# macron.net
KiCad netlist of a schematic drawn in EAGLE
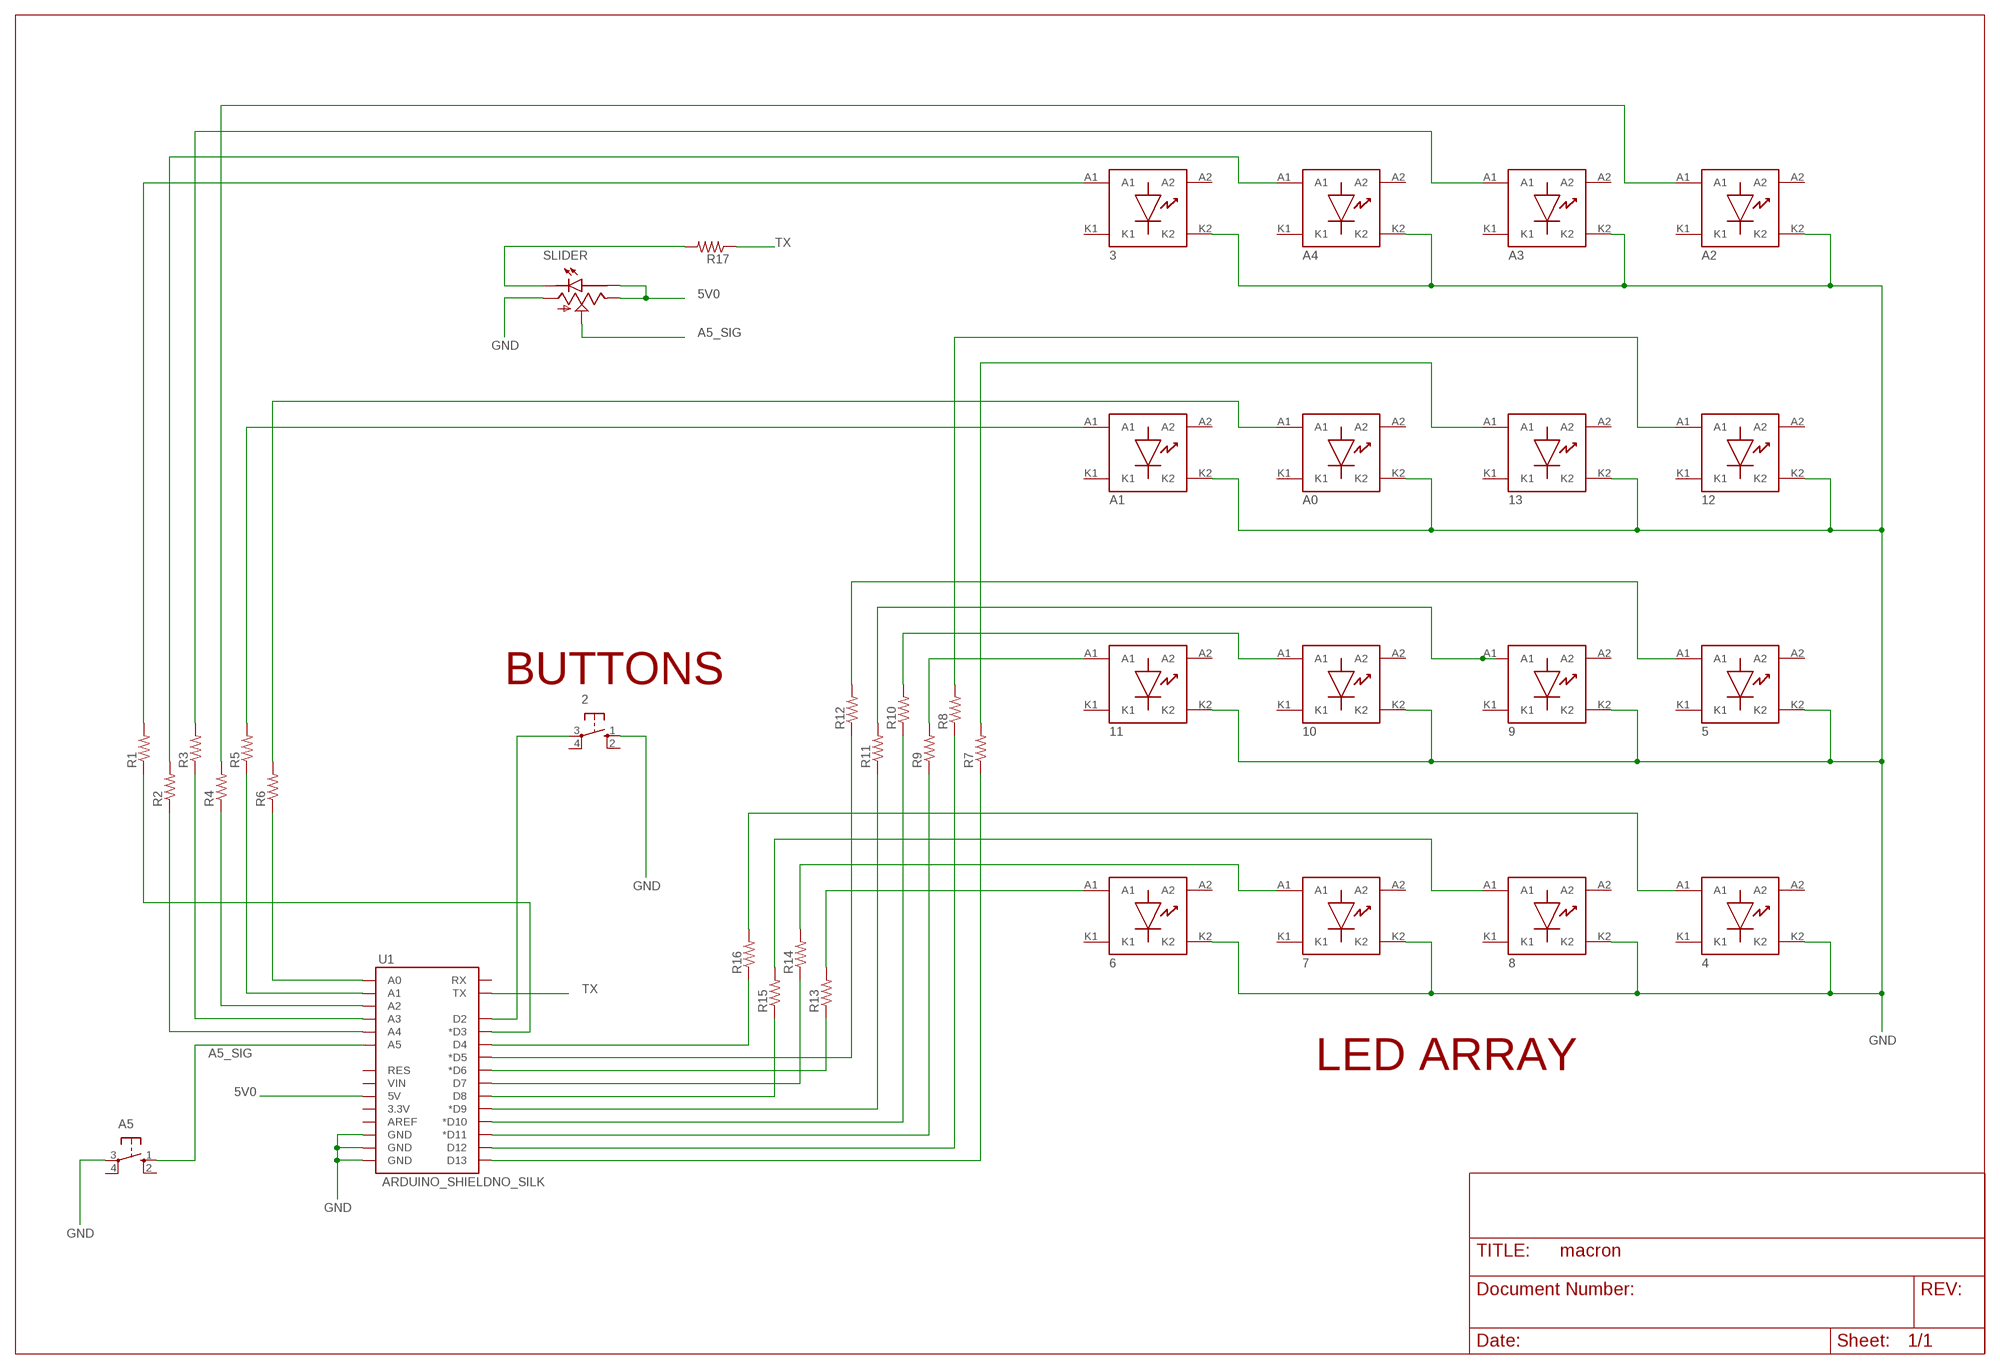
[diagram p0: schematic, sheet 1]

(export (version "E")
  (design (tool "Eeschema 10.0.6"))
  (components
    (comp (ref "2")
      (value "10-XX")
      (footprint "eagle-import:B3F-10XX")
      (fields (field (name "MPN") "B3F-1000"))
      (libsource (lib "eagle-import") (part "10-XX"))
    )
    (comp (ref "3")
      (value "LED_SMT")
      (footprint "eagle-import:AVAGO-SMT-LED")
      (libsource (lib "eagle-import") (part "LED_SMT"))
    )
    (comp (ref "4")
      (value "LED_SMT")
      (footprint "eagle-import:AVAGO-SMT-LED")
      (libsource (lib "eagle-import") (part "LED_SMT"))
    )
    (comp (ref "5")
      (value "LED_SMT")
      (footprint "eagle-import:AVAGO-SMT-LED")
      (libsource (lib "eagle-import") (part "LED_SMT"))
    )
    (comp (ref "6")
      (value "LED_SMT")
      (footprint "eagle-import:AVAGO-SMT-LED")
      (libsource (lib "eagle-import") (part "LED_SMT"))
    )
    (comp (ref "7")
      (value "LED_SMT")
      (footprint "eagle-import:AVAGO-SMT-LED")
      (libsource (lib "eagle-import") (part "LED_SMT"))
    )
    (comp (ref "8")
      (value "LED_SMT")
      (footprint "eagle-import:AVAGO-SMT-LED")
      (libsource (lib "eagle-import") (part "LED_SMT"))
    )
    (comp (ref "9")
      (value "LED_SMT")
      (footprint "eagle-import:AVAGO-SMT-LED")
      (libsource (lib "eagle-import") (part "LED_SMT"))
    )
    (comp (ref "10")
      (value "LED_SMT")
      (footprint "eagle-import:AVAGO-SMT-LED")
      (libsource (lib "eagle-import") (part "LED_SMT"))
    )
    (comp (ref "11")
      (value "LED_SMT")
      (footprint "eagle-import:AVAGO-SMT-LED")
      (libsource (lib "eagle-import") (part "LED_SMT"))
    )
    (comp (ref "12")
      (value "LED_SMT")
      (footprint "eagle-import:AVAGO-SMT-LED")
      (libsource (lib "eagle-import") (part "LED_SMT"))
    )
    (comp (ref "13")
      (value "LED_SMT")
      (footprint "eagle-import:AVAGO-SMT-LED")
      (libsource (lib "eagle-import") (part "LED_SMT"))
    )
    (comp (ref "A0")
      (value "LED_SMT")
      (footprint "eagle-import:AVAGO-SMT-LED")
      (libsource (lib "eagle-import") (part "LED_SMT"))
    )
    (comp (ref "A1")
      (value "LED_SMT")
      (footprint "eagle-import:AVAGO-SMT-LED")
      (libsource (lib "eagle-import") (part "LED_SMT"))
    )
    (comp (ref "A2")
      (value "LED_SMT")
      (footprint "eagle-import:AVAGO-SMT-LED")
      (libsource (lib "eagle-import") (part "LED_SMT"))
    )
    (comp (ref "A3")
      (value "LED_SMT")
      (footprint "eagle-import:AVAGO-SMT-LED")
      (libsource (lib "eagle-import") (part "LED_SMT"))
    )
    (comp (ref "A4")
      (value "LED_SMT")
      (footprint "eagle-import:AVAGO-SMT-LED")
      (libsource (lib "eagle-import") (part "LED_SMT"))
    )
    (comp (ref "A5")
      (value "10-XX")
      (footprint "eagle-import:B3F-10XX")
      (fields (field (name "MPN") "B3F-1000"))
      (libsource (lib "eagle-import") (part "10-XX"))
    )
    (comp (ref "R1")
      (value "R-US_0204/7")
      (footprint "eagle-import:0204_7")
      (libsource (lib "eagle-import") (part "R-US_0204/7"))
    )
    (comp (ref "R2")
      (value "R-US_0204/7")
      (footprint "eagle-import:0204_7")
      (libsource (lib "eagle-import") (part "R-US_0204/7"))
    )
    (comp (ref "R3")
      (value "R-US_0204/7")
      (footprint "eagle-import:0204_7")
      (libsource (lib "eagle-import") (part "R-US_0204/7"))
    )
    (comp (ref "R4")
      (value "R-US_0204/7")
      (footprint "eagle-import:0204_7")
      (libsource (lib "eagle-import") (part "R-US_0204/7"))
    )
    (comp (ref "R5")
      (value "R-US_0204/7")
      (footprint "eagle-import:0204_7")
      (libsource (lib "eagle-import") (part "R-US_0204/7"))
    )
    (comp (ref "R6")
      (value "R-US_0204/7")
      (footprint "eagle-import:0204_7")
      (libsource (lib "eagle-import") (part "R-US_0204/7"))
    )
    (comp (ref "R7")
      (value "R-US_0204/7")
      (footprint "eagle-import:0204_7")
      (libsource (lib "eagle-import") (part "R-US_0204/7"))
    )
    (comp (ref "R8")
      (value "R-US_0204/7")
      (footprint "eagle-import:0204_7")
      (libsource (lib "eagle-import") (part "R-US_0204/7"))
    )
    (comp (ref "R9")
      (value "R-US_0204/7")
      (footprint "eagle-import:0204_7")
      (libsource (lib "eagle-import") (part "R-US_0204/7"))
    )
    (comp (ref "R10")
      (value "R-US_0204/7")
      (footprint "eagle-import:0204_7")
      (libsource (lib "eagle-import") (part "R-US_0204/7"))
    )
    (comp (ref "R11")
      (value "R-US_0204/7")
      (footprint "eagle-import:0204_7")
      (libsource (lib "eagle-import") (part "R-US_0204/7"))
    )
    (comp (ref "R12")
      (value "R-US_0204/7")
      (footprint "eagle-import:0204_7")
      (libsource (lib "eagle-import") (part "R-US_0204/7"))
    )
    (comp (ref "R13")
      (value "R-US_0204/7")
      (footprint "eagle-import:0204_7")
      (libsource (lib "eagle-import") (part "R-US_0204/7"))
    )
    (comp (ref "R14")
      (value "R-US_0204/7")
      (footprint "eagle-import:0204_7")
      (libsource (lib "eagle-import") (part "R-US_0204/7"))
    )
    (comp (ref "R15")
      (value "R-US_0204/7")
      (footprint "eagle-import:0204_7")
      (libsource (lib "eagle-import") (part "R-US_0204/7"))
    )
    (comp (ref "R16")
      (value "R-US_0204/7")
      (footprint "eagle-import:0204_7")
      (libsource (lib "eagle-import") (part "R-US_0204/7"))
    )
    (comp (ref "R17")
      (value "R-US_0204/7")
      (footprint "eagle-import:0204_7")
      (libsource (lib "eagle-import") (part "R-US_0204/7"))
    )
    (comp (ref "SLIDER")
      (value "BOURNS_LED_SLIDER")
      (footprint "eagle-import:BOURNS_45MM_LED_SLIDE_POT")
      (libsource (lib "eagle-import") (part "BOURNS_LED_SLIDER"))
    )
    (comp (ref "U1")
      (value "ARDUINO_SHIELDNO_SILK")
      (footprint "eagle-import:DUEMILANOVE_VIAS")
      (libsource (lib "eagle-import") (part "ARDUINO_SHIELDNO_SILK"))
    )
  )
  (nets
    (net (code "1") (name "/5V0") (class "Default")
      (node (ref "SLIDER") (pin "HIGH_END") (pinfunction "HIGH_HIGH_END") (pintype "passive"))
      (node (ref "SLIDER") (pin "LED+") (pinfunction "A1_LED+") (pintype "passive"))
      (node (ref "U1") (pin "5V") (pinfunction "5V_5V") (pintype "bidirectional"))
    )
    (net (code "2") (name "/A5_SIG") (class "Default")
      (node (ref "A5") (pin "1") (pinfunction "S_1") (pintype "passive"))
      (node (ref "SLIDER") (pin "WIPER") (pinfunction "WIPER_WIPER") (pintype "passive"))
      (node (ref "U1") (pin "A5") (pinfunction "A5_A5") (pintype "bidirectional"))
    )
    (net (code "3") (name "/GND") (class "Default")
      (node (ref "10") (pin "K2") (pinfunction "K2_K2") (pintype "passive"))
      (node (ref "11") (pin "K2") (pinfunction "K2_K2") (pintype "passive"))
      (node (ref "12") (pin "K2") (pinfunction "K2_K2") (pintype "passive"))
      (node (ref "13") (pin "K2") (pinfunction "K2_K2") (pintype "passive"))
      (node (ref "2") (pin "1") (pinfunction "S_1") (pintype "passive"))
      (node (ref "3") (pin "K2") (pinfunction "K2_K2") (pintype "passive"))
      (node (ref "4") (pin "K2") (pinfunction "K2_K2") (pintype "passive"))
      (node (ref "5") (pin "K2") (pinfunction "K2_K2") (pintype "passive"))
      (node (ref "6") (pin "K2") (pinfunction "K2_K2") (pintype "passive"))
      (node (ref "7") (pin "K2") (pinfunction "K2_K2") (pintype "passive"))
      (node (ref "8") (pin "K2") (pinfunction "K2_K2") (pintype "passive"))
      (node (ref "9") (pin "K2") (pinfunction "K2_K2") (pintype "passive"))
      (node (ref "A0") (pin "K2") (pinfunction "K2_K2") (pintype "passive"))
      (node (ref "A1") (pin "K2") (pinfunction "K2_K2") (pintype "passive"))
      (node (ref "A2") (pin "K2") (pinfunction "K2_K2") (pintype "passive"))
      (node (ref "A3") (pin "K2") (pinfunction "K2_K2") (pintype "passive"))
      (node (ref "A4") (pin "K2") (pinfunction "K2_K2") (pintype "passive"))
      (node (ref "A5") (pin "3") (pinfunction "P_3") (pintype "passive"))
      (node (ref "SLIDER") (pin "LOW_END") (pinfunction "LOW_LOW_END") (pintype "passive"))
      (node (ref "U1") (pin "GND@0") (pinfunction "GND_GND@0") (pintype "bidirectional"))
      (node (ref "U1") (pin "GND@1") (pinfunction "GND_GND@1") (pintype "bidirectional"))
      (node (ref "U1") (pin "GND@2") (pinfunction "GND_GND@2") (pintype "bidirectional"))
    )
    (net (code "4") (name "/TX") (class "Default")
      (node (ref "R17") (pin "1") (pinfunction "1_1") (pintype "passive"))
      (node (ref "U1") (pin "TX") (pinfunction "TX_TX") (pintype "bidirectional"))
    )
    (net (code "5") (name "Net-(2-P)") (class "Default")
      (node (ref "2") (pin "3") (pinfunction "P_3") (pintype "passive"))
      (node (ref "U1") (pin "D2") (pinfunction "D2_D2") (pintype "bidirectional"))
    )
    (net (code "6") (name "Net-(3-PadA1)") (class "Default")
      (node (ref "3") (pin "A1") (pinfunction "A1_A1") (pintype "passive"))
      (node (ref "R1") (pin "2") (pinfunction "2_2") (pintype "passive"))
    )
    (net (code "7") (name "Net-(4-PadA1)") (class "Default")
      (node (ref "4") (pin "A1") (pinfunction "A1_A1") (pintype "passive"))
      (node (ref "R16") (pin "2") (pinfunction "2_2") (pintype "passive"))
    )
    (net (code "8") (name "Net-(5-PadA1)") (class "Default")
      (node (ref "5") (pin "A1") (pinfunction "A1_A1") (pintype "passive"))
      (node (ref "R12") (pin "2") (pinfunction "2_2") (pintype "passive"))
    )
    (net (code "9") (name "Net-(6-PadA1)") (class "Default")
      (node (ref "6") (pin "A1") (pinfunction "A1_A1") (pintype "passive"))
      (node (ref "R13") (pin "2") (pinfunction "2_2") (pintype "passive"))
    )
    (net (code "10") (name "Net-(7-PadA1)") (class "Default")
      (node (ref "7") (pin "A1") (pinfunction "A1_A1") (pintype "passive"))
      (node (ref "R14") (pin "2") (pinfunction "2_2") (pintype "passive"))
    )
    (net (code "11") (name "Net-(8-PadA1)") (class "Default")
      (node (ref "8") (pin "A1") (pinfunction "A1_A1") (pintype "passive"))
      (node (ref "R15") (pin "2") (pinfunction "2_2") (pintype "passive"))
    )
    (net (code "12") (name "Net-(9-PadA1)") (class "Default")
      (node (ref "9") (pin "A1") (pinfunction "A1_A1") (pintype "passive"))
      (node (ref "R11") (pin "2") (pinfunction "2_2") (pintype "passive"))
    )
    (net (code "13") (name "Net-(10-PadA1)") (class "Default")
      (node (ref "10") (pin "A1") (pinfunction "A1_A1") (pintype "passive"))
      (node (ref "R10") (pin "2") (pinfunction "2_2") (pintype "passive"))
    )
    (net (code "14") (name "Net-(11-PadA1)") (class "Default")
      (node (ref "11") (pin "A1") (pinfunction "A1_A1") (pintype "passive"))
      (node (ref "R9") (pin "2") (pinfunction "2_2") (pintype "passive"))
    )
    (net (code "15") (name "Net-(12-PadA1)") (class "Default")
      (node (ref "12") (pin "A1") (pinfunction "A1_A1") (pintype "passive"))
      (node (ref "R8") (pin "2") (pinfunction "2_2") (pintype "passive"))
    )
    (net (code "16") (name "Net-(13-PadA1)") (class "Default")
      (node (ref "13") (pin "A1") (pinfunction "A1_A1") (pintype "passive"))
      (node (ref "R7") (pin "2") (pinfunction "2_2") (pintype "passive"))
    )
    (net (code "17") (name "Net-(A0-PadA1)") (class "Default")
      (node (ref "A0") (pin "A1") (pinfunction "A1_A1") (pintype "passive"))
      (node (ref "R6") (pin "2") (pinfunction "2_2") (pintype "passive"))
    )
    (net (code "18") (name "Net-(A1-PadA1)") (class "Default")
      (node (ref "A1") (pin "A1") (pinfunction "A1_A1") (pintype "passive"))
      (node (ref "R5") (pin "2") (pinfunction "2_2") (pintype "passive"))
    )
    (net (code "19") (name "Net-(A2-PadA1)") (class "Default")
      (node (ref "A2") (pin "A1") (pinfunction "A1_A1") (pintype "passive"))
      (node (ref "R4") (pin "2") (pinfunction "2_2") (pintype "passive"))
    )
    (net (code "20") (name "Net-(A3-PadA1)") (class "Default")
      (node (ref "A3") (pin "A1") (pinfunction "A1_A1") (pintype "passive"))
      (node (ref "R3") (pin "2") (pinfunction "2_2") (pintype "passive"))
    )
    (net (code "21") (name "Net-(A4-PadA1)") (class "Default")
      (node (ref "A4") (pin "A1") (pinfunction "A1_A1") (pintype "passive"))
      (node (ref "R2") (pin "2") (pinfunction "2_2") (pintype "passive"))
    )
    (net (code "22") (name "Net-(R2-Pad1)") (class "Default")
      (node (ref "R2") (pin "1") (pinfunction "1_1") (pintype "passive"))
      (node (ref "U1") (pin "A4") (pinfunction "A4_A4") (pintype "bidirectional"))
    )
    (net (code "23") (name "Net-(R3-Pad1)") (class "Default")
      (node (ref "R3") (pin "1") (pinfunction "1_1") (pintype "passive"))
      (node (ref "U1") (pin "A3") (pinfunction "A3_A3") (pintype "bidirectional"))
    )
    (net (code "24") (name "Net-(R4-Pad1)") (class "Default")
      (node (ref "R4") (pin "1") (pinfunction "1_1") (pintype "passive"))
      (node (ref "U1") (pin "A2") (pinfunction "A2_A2") (pintype "bidirectional"))
    )
    (net (code "25") (name "Net-(R5-Pad1)") (class "Default")
      (node (ref "R5") (pin "1") (pinfunction "1_1") (pintype "passive"))
      (node (ref "U1") (pin "A1") (pinfunction "A1_A1") (pintype "bidirectional"))
    )
    (net (code "26") (name "Net-(R6-Pad1)") (class "Default")
      (node (ref "R6") (pin "1") (pinfunction "1_1") (pintype "passive"))
      (node (ref "U1") (pin "A0") (pinfunction "A0_A0") (pintype "bidirectional"))
    )
    (net (code "27") (name "Net-(R7-Pad1)") (class "Default")
      (node (ref "R7") (pin "1") (pinfunction "1_1") (pintype "passive"))
      (node (ref "U1") (pin "D13") (pinfunction "D13_D13") (pintype "bidirectional"))
    )
    (net (code "28") (name "Net-(R8-Pad1)") (class "Default")
      (node (ref "R8") (pin "1") (pinfunction "1_1") (pintype "passive"))
      (node (ref "U1") (pin "D12") (pinfunction "D12_D12") (pintype "bidirectional"))
    )
    (net (code "29") (name "Net-(R14-Pad1)") (class "Default")
      (node (ref "R14") (pin "1") (pinfunction "1_1") (pintype "passive"))
      (node (ref "U1") (pin "D7") (pinfunction "D7_D7") (pintype "bidirectional"))
    )
    (net (code "30") (name "Net-(R15-Pad1)") (class "Default")
      (node (ref "R15") (pin "1") (pinfunction "1_1") (pintype "passive"))
      (node (ref "U1") (pin "D8") (pinfunction "D8_D8") (pintype "bidirectional"))
    )
    (net (code "31") (name "Net-(R16-Pad1)") (class "Default")
      (node (ref "R16") (pin "1") (pinfunction "1_1") (pintype "passive"))
      (node (ref "U1") (pin "D4") (pinfunction "D4_D4") (pintype "bidirectional"))
    )
    (net (code "32") (name "Net-(SLIDER-C)") (class "Default")
      (node (ref "R17") (pin "2") (pinfunction "2_2") (pintype "passive"))
      (node (ref "SLIDER") (pin "LED-") (pinfunction "C_LED-") (pintype "passive"))
    )
    (net (code "33") (name "Net-(U1-*D3)") (class "Default")
      (node (ref "R1") (pin "1") (pinfunction "1_1") (pintype "passive"))
      (node (ref "U1") (pin "D3") (pinfunction "*D3_D3") (pintype "bidirectional"))
    )
    (net (code "34") (name "Net-(U1-*D5)") (class "Default")
      (node (ref "R12") (pin "1") (pinfunction "1_1") (pintype "passive"))
      (node (ref "U1") (pin "D5") (pinfunction "*D5_D5") (pintype "bidirectional"))
    )
    (net (code "35") (name "Net-(U1-*D6)") (class "Default")
      (node (ref "R13") (pin "1") (pinfunction "1_1") (pintype "passive"))
      (node (ref "U1") (pin "D6") (pinfunction "*D6_D6") (pintype "bidirectional"))
    )
    (net (code "36") (name "Net-(U1-*D9)") (class "Default")
      (node (ref "R11") (pin "1") (pinfunction "1_1") (pintype "passive"))
      (node (ref "U1") (pin "D9") (pinfunction "*D9_D9") (pintype "bidirectional"))
    )
    (net (code "37") (name "Net-(U1-*D10)") (class "Default")
      (node (ref "R10") (pin "1") (pinfunction "1_1") (pintype "passive"))
      (node (ref "U1") (pin "D10") (pinfunction "*D10_D10") (pintype "bidirectional"))
    )
    (net (code "38") (name "Net-(U1-*D11)") (class "Default")
      (node (ref "R9") (pin "1") (pinfunction "1_1") (pintype "passive"))
      (node (ref "U1") (pin "D11") (pinfunction "*D11_D11") (pintype "bidirectional"))
    )
    (net (code "39") (name "unconnected-(2-P1-Pad4)") (class "Default")
      (node (ref "2") (pin "4") (pinfunction "P1_4") (pintype "passive"))
    )
    (net (code "40") (name "unconnected-(2-S1-Pad2)") (class "Default")
      (node (ref "2") (pin "2") (pinfunction "S1_2") (pintype "passive"))
    )
    (net (code "41") (name "unconnected-(3-PadA2)") (class "Default")
      (node (ref "3") (pin "A2") (pinfunction "A2_A2") (pintype "passive"))
    )
    (net (code "42") (name "unconnected-(3-PadK1)") (class "Default")
      (node (ref "3") (pin "K1") (pinfunction "K1_K1") (pintype "passive"))
    )
    (net (code "43") (name "unconnected-(4-PadA2)") (class "Default")
      (node (ref "4") (pin "A2") (pinfunction "A2_A2") (pintype "passive"))
    )
    (net (code "44") (name "unconnected-(4-PadK1)") (class "Default")
      (node (ref "4") (pin "K1") (pinfunction "K1_K1") (pintype "passive"))
    )
    (net (code "45") (name "unconnected-(5-PadA2)") (class "Default")
      (node (ref "5") (pin "A2") (pinfunction "A2_A2") (pintype "passive"))
    )
    (net (code "46") (name "unconnected-(5-PadK1)") (class "Default")
      (node (ref "5") (pin "K1") (pinfunction "K1_K1") (pintype "passive"))
    )
    (net (code "47") (name "unconnected-(6-PadA2)") (class "Default")
      (node (ref "6") (pin "A2") (pinfunction "A2_A2") (pintype "passive"))
    )
    (net (code "48") (name "unconnected-(6-PadK1)") (class "Default")
      (node (ref "6") (pin "K1") (pinfunction "K1_K1") (pintype "passive"))
    )
    (net (code "49") (name "unconnected-(7-PadA2)") (class "Default")
      (node (ref "7") (pin "A2") (pinfunction "A2_A2") (pintype "passive"))
    )
    (net (code "50") (name "unconnected-(7-PadK1)") (class "Default")
      (node (ref "7") (pin "K1") (pinfunction "K1_K1") (pintype "passive"))
    )
    (net (code "51") (name "unconnected-(8-PadA2)") (class "Default")
      (node (ref "8") (pin "A2") (pinfunction "A2_A2") (pintype "passive"))
    )
    (net (code "52") (name "unconnected-(8-PadK1)") (class "Default")
      (node (ref "8") (pin "K1") (pinfunction "K1_K1") (pintype "passive"))
    )
    (net (code "53") (name "unconnected-(9-PadA2)") (class "Default")
      (node (ref "9") (pin "A2") (pinfunction "A2_A2") (pintype "passive"))
    )
    (net (code "54") (name "unconnected-(9-PadK1)") (class "Default")
      (node (ref "9") (pin "K1") (pinfunction "K1_K1") (pintype "passive"))
    )
    (net (code "55") (name "unconnected-(10-PadA2)") (class "Default")
      (node (ref "10") (pin "A2") (pinfunction "A2_A2") (pintype "passive"))
    )
    (net (code "56") (name "unconnected-(10-PadK1)") (class "Default")
      (node (ref "10") (pin "K1") (pinfunction "K1_K1") (pintype "passive"))
    )
    (net (code "57") (name "unconnected-(11-PadA2)") (class "Default")
      (node (ref "11") (pin "A2") (pinfunction "A2_A2") (pintype "passive"))
    )
    (net (code "58") (name "unconnected-(11-PadK1)") (class "Default")
      (node (ref "11") (pin "K1") (pinfunction "K1_K1") (pintype "passive"))
    )
    (net (code "59") (name "unconnected-(12-PadA2)") (class "Default")
      (node (ref "12") (pin "A2") (pinfunction "A2_A2") (pintype "passive"))
    )
    (net (code "60") (name "unconnected-(12-PadK1)") (class "Default")
      (node (ref "12") (pin "K1") (pinfunction "K1_K1") (pintype "passive"))
    )
    (net (code "61") (name "unconnected-(13-PadA2)") (class "Default")
      (node (ref "13") (pin "A2") (pinfunction "A2_A2") (pintype "passive"))
    )
    (net (code "62") (name "unconnected-(13-PadK1)") (class "Default")
      (node (ref "13") (pin "K1") (pinfunction "K1_K1") (pintype "passive"))
    )
    (net (code "63") (name "unconnected-(A0-PadA2)") (class "Default")
      (node (ref "A0") (pin "A2") (pinfunction "A2_A2") (pintype "passive"))
    )
    (net (code "64") (name "unconnected-(A0-PadK1)") (class "Default")
      (node (ref "A0") (pin "K1") (pinfunction "K1_K1") (pintype "passive"))
    )
    (net (code "65") (name "unconnected-(A1-PadA2)") (class "Default")
      (node (ref "A1") (pin "A2") (pinfunction "A2_A2") (pintype "passive"))
    )
    (net (code "66") (name "unconnected-(A1-PadK1)") (class "Default")
      (node (ref "A1") (pin "K1") (pinfunction "K1_K1") (pintype "passive"))
    )
    (net (code "67") (name "unconnected-(A2-PadA2)") (class "Default")
      (node (ref "A2") (pin "A2") (pinfunction "A2_A2") (pintype "passive"))
    )
    (net (code "68") (name "unconnected-(A2-PadK1)") (class "Default")
      (node (ref "A2") (pin "K1") (pinfunction "K1_K1") (pintype "passive"))
    )
    (net (code "69") (name "unconnected-(A3-PadA2)") (class "Default")
      (node (ref "A3") (pin "A2") (pinfunction "A2_A2") (pintype "passive"))
    )
    (net (code "70") (name "unconnected-(A3-PadK1)") (class "Default")
      (node (ref "A3") (pin "K1") (pinfunction "K1_K1") (pintype "passive"))
    )
    (net (code "71") (name "unconnected-(A4-PadA2)") (class "Default")
      (node (ref "A4") (pin "A2") (pinfunction "A2_A2") (pintype "passive"))
    )
    (net (code "72") (name "unconnected-(A4-PadK1)") (class "Default")
      (node (ref "A4") (pin "K1") (pinfunction "K1_K1") (pintype "passive"))
    )
    (net (code "73") (name "unconnected-(A5-P1-Pad4)") (class "Default")
      (node (ref "A5") (pin "4") (pinfunction "P1_4") (pintype "passive"))
    )
    (net (code "74") (name "unconnected-(A5-S1-Pad2)") (class "Default")
      (node (ref "A5") (pin "2") (pinfunction "S1_2") (pintype "passive"))
    )
    (net (code "75") (name "unconnected-(U1-Pad3.3V)") (class "Default")
      (node (ref "U1") (pin "3.3V") (pinfunction "3.3V_3.3V") (pintype "bidirectional"))
    )
    (net (code "76") (name "unconnected-(U1-PadAREF)") (class "Default")
      (node (ref "U1") (pin "AREF") (pinfunction "AREF_AREF") (pintype "bidirectional"))
    )
    (net (code "77") (name "unconnected-(U1-PadRES)") (class "Default")
      (node (ref "U1") (pin "RES") (pinfunction "RES_RES") (pintype "bidirectional"))
    )
    (net (code "78") (name "unconnected-(U1-PadRX)") (class "Default")
      (node (ref "U1") (pin "RX") (pinfunction "RX_RX") (pintype "bidirectional"))
    )
    (net (code "79") (name "unconnected-(U1-PadVIN)") (class "Default")
      (node (ref "U1") (pin "VIN") (pinfunction "VIN_VIN") (pintype "bidirectional"))
    )
  )
)
